# Skaarhoj_BI8-SE-C201.net
KiCad netlist of a schematic drawn in EAGLE
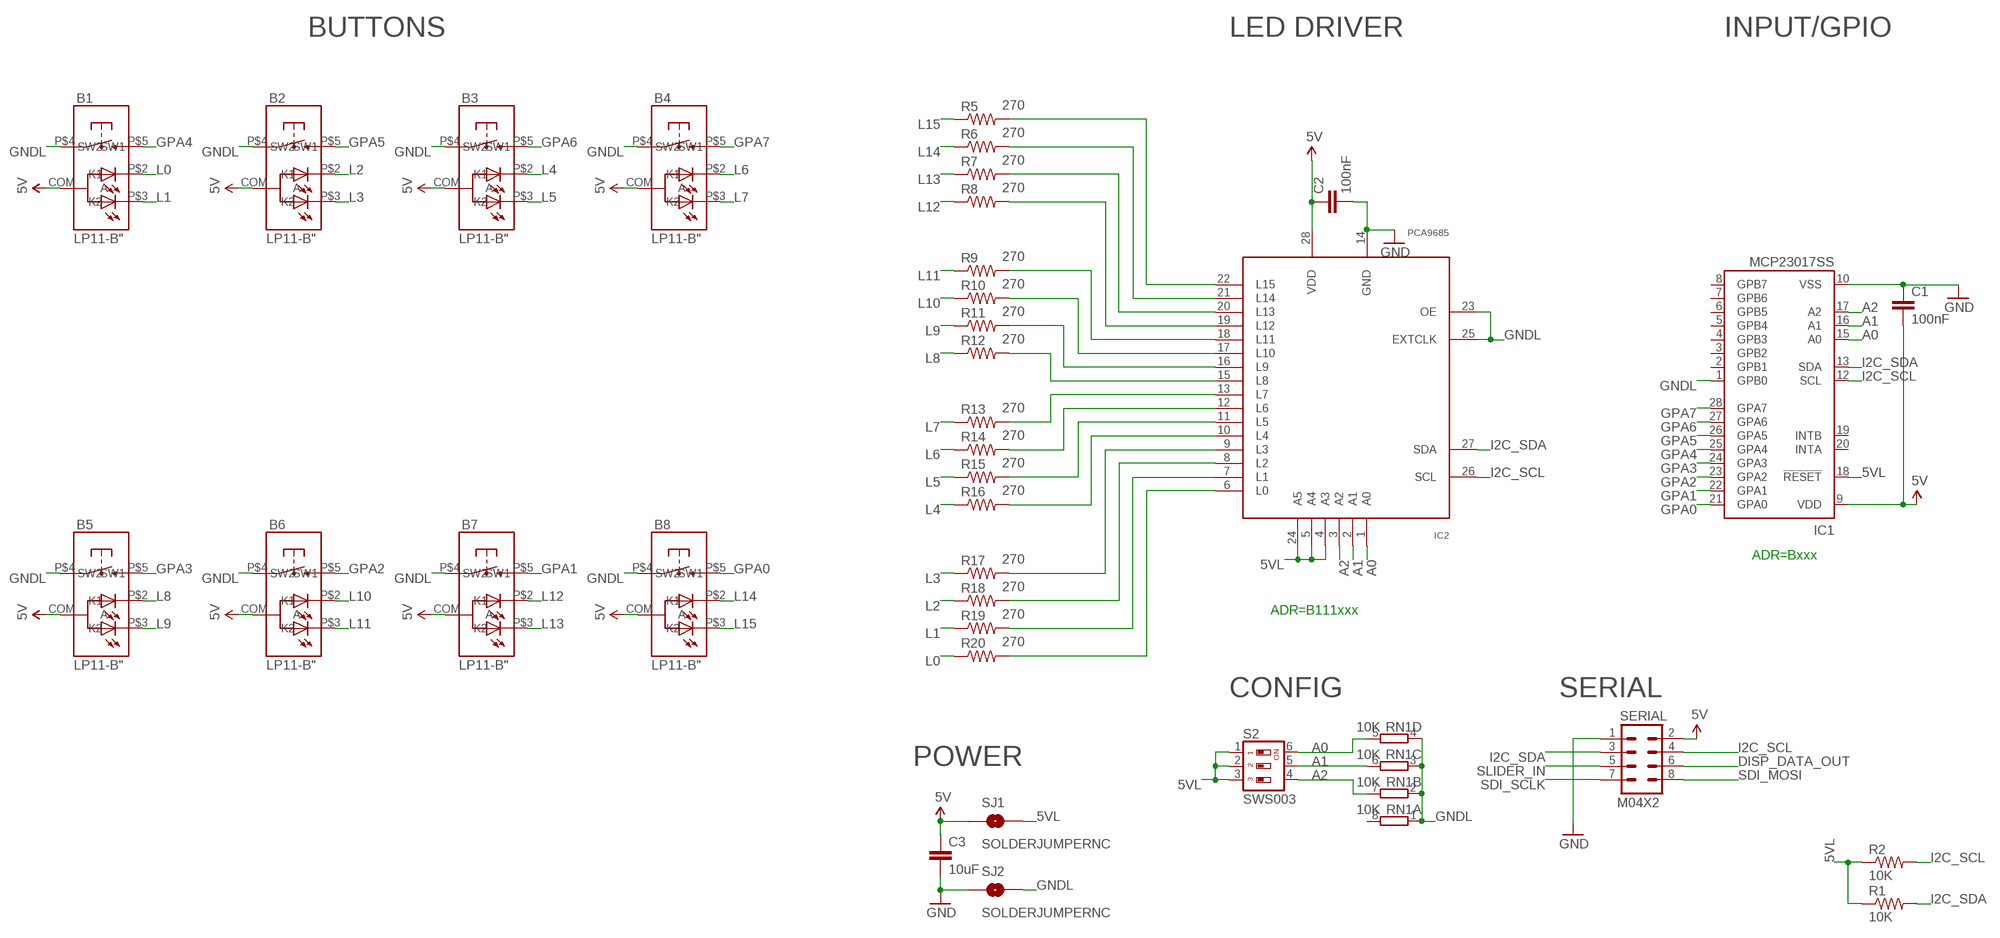
[diagram p0: schematic, sheet 1]

(export (version "E")
  (design (tool "Eeschema 10.0.6"))
  (components
    (comp (ref "B1")
      (value "LP11-B\"")
      (footprint "eagle-import:LP11")
      (libsource (lib "eagle-import") (part "LP11-B{dblquote}"))
    )
    (comp (ref "B2")
      (value "LP11-B\"")
      (footprint "eagle-import:LP11")
      (libsource (lib "eagle-import") (part "LP11-B{dblquote}"))
    )
    (comp (ref "B3")
      (value "LP11-B\"")
      (footprint "eagle-import:LP11")
      (libsource (lib "eagle-import") (part "LP11-B{dblquote}"))
    )
    (comp (ref "B4")
      (value "LP11-B\"")
      (footprint "eagle-import:LP11")
      (libsource (lib "eagle-import") (part "LP11-B{dblquote}"))
    )
    (comp (ref "B5")
      (value "LP11-B\"")
      (footprint "eagle-import:LP11")
      (libsource (lib "eagle-import") (part "LP11-B{dblquote}"))
    )
    (comp (ref "B6")
      (value "LP11-B\"")
      (footprint "eagle-import:LP11")
      (libsource (lib "eagle-import") (part "LP11-B{dblquote}"))
    )
    (comp (ref "B7")
      (value "LP11-B\"")
      (footprint "eagle-import:LP11")
      (libsource (lib "eagle-import") (part "LP11-B{dblquote}"))
    )
    (comp (ref "B8")
      (value "LP11-B\"")
      (footprint "eagle-import:LP11")
      (libsource (lib "eagle-import") (part "LP11-B{dblquote}"))
    )
    (comp (ref "C1")
      (value "100nF")
      (footprint "eagle-import:0603-CAP")
      (libsource (lib "eagle-import") (part "CAP0603-CAP"))
    )
    (comp (ref "C2")
      (value "100nF")
      (footprint "eagle-import:0603-CAP")
      (libsource (lib "eagle-import") (part "CAP0603-CAP"))
    )
    (comp (ref "C3")
      (value "10uF")
      (footprint "eagle-import:0805")
      (libsource (lib "eagle-import") (part "CAP0805"))
    )
    (comp (ref "IC1")
      (value "MCP23017SS")
      (footprint "eagle-import:SSOP28")
      (fields
        (field (name "MF") "MICROCHIP")
        (field (name "MPN") "MCP23017-E/SS")
        (field (name "MPN_1") "MCP23017-E/SS")
        (field (name "OC_FARNELL") "1467674")
        (field (name "OC_NEWARK") "31K2960")
      )
      (libsource (lib "eagle-import") (part "MCP23017SS"))
    )
    (comp (ref "IC2")
      (value "PCA9685")
      (footprint "eagle-import:TSSOP28")
      (libsource (lib "eagle-import") (part "PCA9685"))
    )
    (comp (ref "R1")
      (value "10K")
      (footprint "eagle-import:0603-RES")
      (libsource (lib "eagle-import") (part "RESISTOR0603-RES"))
    )
    (comp (ref "R2")
      (value "10K")
      (footprint "eagle-import:0603-RES")
      (libsource (lib "eagle-import") (part "RESISTOR0603-RES"))
    )
    (comp (ref "R5")
      (value "270")
      (footprint "eagle-import:0603-RES")
      (libsource (lib "eagle-import") (part "RESISTOR0603-RES"))
    )
    (comp (ref "R6")
      (value "270")
      (footprint "eagle-import:0603-RES")
      (libsource (lib "eagle-import") (part "RESISTOR0603-RES"))
    )
    (comp (ref "R7")
      (value "270")
      (footprint "eagle-import:0603-RES")
      (libsource (lib "eagle-import") (part "RESISTOR0603-RES"))
    )
    (comp (ref "R8")
      (value "270")
      (footprint "eagle-import:0603-RES")
      (libsource (lib "eagle-import") (part "RESISTOR0603-RES"))
    )
    (comp (ref "R9")
      (value "270")
      (footprint "eagle-import:0603-RES")
      (libsource (lib "eagle-import") (part "RESISTOR0603-RES"))
    )
    (comp (ref "R10")
      (value "270")
      (footprint "eagle-import:0603-RES")
      (libsource (lib "eagle-import") (part "RESISTOR0603-RES"))
    )
    (comp (ref "R11")
      (value "270")
      (footprint "eagle-import:0603-RES")
      (libsource (lib "eagle-import") (part "RESISTOR0603-RES"))
    )
    (comp (ref "R12")
      (value "270")
      (footprint "eagle-import:0603-RES")
      (libsource (lib "eagle-import") (part "RESISTOR0603-RES"))
    )
    (comp (ref "R13")
      (value "270")
      (footprint "eagle-import:0603-RES")
      (libsource (lib "eagle-import") (part "RESISTOR0603-RES"))
    )
    (comp (ref "R14")
      (value "270")
      (footprint "eagle-import:0603-RES")
      (libsource (lib "eagle-import") (part "RESISTOR0603-RES"))
    )
    (comp (ref "R15")
      (value "270")
      (footprint "eagle-import:0603-RES")
      (libsource (lib "eagle-import") (part "RESISTOR0603-RES"))
    )
    (comp (ref "R16")
      (value "270")
      (footprint "eagle-import:0603-RES")
      (libsource (lib "eagle-import") (part "RESISTOR0603-RES"))
    )
    (comp (ref "R17")
      (value "270")
      (footprint "eagle-import:0603-RES")
      (libsource (lib "eagle-import") (part "RESISTOR0603-RES"))
    )
    (comp (ref "R18")
      (value "270")
      (footprint "eagle-import:0603-RES")
      (libsource (lib "eagle-import") (part "RESISTOR0603-RES"))
    )
    (comp (ref "R19")
      (value "270")
      (footprint "eagle-import:0603-RES")
      (libsource (lib "eagle-import") (part "RESISTOR0603-RES"))
    )
    (comp (ref "R20")
      (value "270")
      (footprint "eagle-import:0603-RES")
      (libsource (lib "eagle-import") (part "RESISTOR0603-RES"))
    )
    (comp (ref "RN1")
      (value "10K")
      (footprint "eagle-import:CAY16_HAND")
      (libsource (lib "eagle-import") (part "4R-NCAY16"))
    )
    (comp (ref "S2")
      (value "SWS003")
      (footprint "eagle-import:SMS-003")
      (libsource (lib "eagle-import") (part "SWS003"))
    )
    (comp (ref "SERIAL")
      (value "M04X2")
      (footprint "eagle-import:2X4")
      (libsource (lib "eagle-import") (part "M04X2"))
    )
    (comp (ref "SJ1")
      (value "SOLDERJUMPERNC")
      (footprint "eagle-import:SJ_2S")
      (libsource (lib "eagle-import") (part "SOLDERJUMPERNC"))
    )
    (comp (ref "SJ2")
      (value "SOLDERJUMPERNC")
      (footprint "eagle-import:SJ_2S")
      (libsource (lib "eagle-import") (part "SOLDERJUMPERNC"))
    )
  )
  (nets
    (net (code "1") (name "/5VL") (class "Default")
      (node (ref "IC1") (pin "18") (pinfunction "~{RESET}_18") (pintype "input"))
      (node (ref "IC2") (pin "24") (pinfunction "A5_24") (pintype "input"))
      (node (ref "IC2") (pin "4") (pinfunction "A3_4") (pintype "input"))
      (node (ref "IC2") (pin "5") (pinfunction "A4_5") (pintype "input"))
      (node (ref "R1") (pin "1") (pinfunction "1_1") (pintype "passive"))
      (node (ref "R2") (pin "1") (pinfunction "1_1") (pintype "passive"))
      (node (ref "S2") (pin "1") (pinfunction "1_1") (pintype "passive"))
      (node (ref "S2") (pin "2") (pinfunction "2_2") (pintype "passive"))
      (node (ref "S2") (pin "3") (pinfunction "3_3") (pintype "passive"))
      (node (ref "SJ1") (pin "2") (pinfunction "2_2") (pintype "passive"))
    )
    (net (code "2") (name "/A0") (class "Default")
      (node (ref "IC1") (pin "15") (pinfunction "A0_15") (pintype "input"))
      (node (ref "IC2") (pin "1") (pinfunction "A0_1") (pintype "input"))
      (node (ref "RN1") (pin "5") (pinfunction "2_5") (pintype "passive"))
      (node (ref "S2") (pin "6") (pinfunction "6_6") (pintype "passive"))
    )
    (net (code "3") (name "/A1") (class "Default")
      (node (ref "IC1") (pin "16") (pinfunction "A1_16") (pintype "input"))
      (node (ref "IC2") (pin "2") (pinfunction "A1_2") (pintype "input"))
      (node (ref "RN1") (pin "6") (pinfunction "2_6") (pintype "passive"))
      (node (ref "S2") (pin "5") (pinfunction "5_5") (pintype "passive"))
    )
    (net (code "4") (name "/A2") (class "Default")
      (node (ref "IC1") (pin "17") (pinfunction "A2_17") (pintype "input"))
      (node (ref "IC2") (pin "3") (pinfunction "A2_3") (pintype "input"))
      (node (ref "RN1") (pin "7") (pinfunction "2_7") (pintype "passive"))
      (node (ref "S2") (pin "4") (pinfunction "4_4") (pintype "passive"))
    )
    (net (code "5") (name "/DISP_DATA_OUT") (class "Default")
      (node (ref "SERIAL") (pin "6") (pinfunction "6_6") (pintype "passive"))
    )
    (net (code "6") (name "/GNDL") (class "Default")
      (node (ref "B1") (pin "P$4") (pinfunction "SW1_P$4") (pintype "bidirectional"))
      (node (ref "B2") (pin "P$4") (pinfunction "SW1_P$4") (pintype "bidirectional"))
      (node (ref "B3") (pin "P$4") (pinfunction "SW1_P$4") (pintype "bidirectional"))
      (node (ref "B4") (pin "P$4") (pinfunction "SW1_P$4") (pintype "bidirectional"))
      (node (ref "B5") (pin "P$4") (pinfunction "SW1_P$4") (pintype "bidirectional"))
      (node (ref "B6") (pin "P$4") (pinfunction "SW1_P$4") (pintype "bidirectional"))
      (node (ref "B7") (pin "P$4") (pinfunction "SW1_P$4") (pintype "bidirectional"))
      (node (ref "B8") (pin "P$4") (pinfunction "SW1_P$4") (pintype "bidirectional"))
      (node (ref "IC1") (pin "1") (pinfunction "GPB0_1") (pintype "bidirectional"))
      (node (ref "IC2") (pin "23") (pinfunction "OE_23") (pintype "input"))
      (node (ref "IC2") (pin "25") (pinfunction "EXTCLK_25") (pintype "input"))
      (node (ref "RN1") (pin "1") (pinfunction "1_1") (pintype "passive"))
      (node (ref "RN1") (pin "2") (pinfunction "1_2") (pintype "passive"))
      (node (ref "RN1") (pin "3") (pinfunction "1_3") (pintype "passive"))
      (node (ref "RN1") (pin "4") (pinfunction "1_4") (pintype "passive"))
      (node (ref "SJ2") (pin "2") (pinfunction "2_2") (pintype "passive"))
    )
    (net (code "7") (name "/GPA0") (class "Default")
      (node (ref "B8") (pin "P$5") (pinfunction "SW2_P$5") (pintype "bidirectional"))
      (node (ref "IC1") (pin "21") (pinfunction "GPA0_21") (pintype "bidirectional"))
    )
    (net (code "8") (name "/GPA1") (class "Default")
      (node (ref "B7") (pin "P$5") (pinfunction "SW2_P$5") (pintype "bidirectional"))
      (node (ref "IC1") (pin "22") (pinfunction "GPA1_22") (pintype "bidirectional"))
    )
    (net (code "9") (name "/GPA2") (class "Default")
      (node (ref "B6") (pin "P$5") (pinfunction "SW2_P$5") (pintype "bidirectional"))
      (node (ref "IC1") (pin "23") (pinfunction "GPA2_23") (pintype "bidirectional"))
    )
    (net (code "10") (name "/GPA3") (class "Default")
      (node (ref "B5") (pin "P$5") (pinfunction "SW2_P$5") (pintype "bidirectional"))
      (node (ref "IC1") (pin "24") (pinfunction "GPA3_24") (pintype "bidirectional"))
    )
    (net (code "11") (name "/GPA4") (class "Default")
      (node (ref "B1") (pin "P$5") (pinfunction "SW2_P$5") (pintype "bidirectional"))
      (node (ref "IC1") (pin "25") (pinfunction "GPA4_25") (pintype "bidirectional"))
    )
    (net (code "12") (name "/GPA5") (class "Default")
      (node (ref "B2") (pin "P$5") (pinfunction "SW2_P$5") (pintype "bidirectional"))
      (node (ref "IC1") (pin "26") (pinfunction "GPA5_26") (pintype "bidirectional"))
    )
    (net (code "13") (name "/GPA6") (class "Default")
      (node (ref "B3") (pin "P$5") (pinfunction "SW2_P$5") (pintype "bidirectional"))
      (node (ref "IC1") (pin "27") (pinfunction "GPA6_27") (pintype "bidirectional"))
    )
    (net (code "14") (name "/GPA7") (class "Default")
      (node (ref "B4") (pin "P$5") (pinfunction "SW2_P$5") (pintype "bidirectional"))
      (node (ref "IC1") (pin "28") (pinfunction "GPA7_28") (pintype "bidirectional"))
    )
    (net (code "15") (name "/I2C_SCL") (class "Default")
      (node (ref "IC1") (pin "12") (pinfunction "SCL_12") (pintype "input"))
      (node (ref "IC2") (pin "26") (pinfunction "SCL_26") (pintype "input"))
      (node (ref "R2") (pin "2") (pinfunction "2_2") (pintype "passive"))
      (node (ref "SERIAL") (pin "4") (pinfunction "4_4") (pintype "passive"))
    )
    (net (code "16") (name "/I2C_SDA") (class "Default")
      (node (ref "IC1") (pin "13") (pinfunction "SDA_13") (pintype "bidirectional"))
      (node (ref "IC2") (pin "27") (pinfunction "SDA_27") (pintype "input"))
      (node (ref "R1") (pin "2") (pinfunction "2_2") (pintype "passive"))
      (node (ref "SERIAL") (pin "3") (pinfunction "3_3") (pintype "passive"))
    )
    (net (code "17") (name "/L0") (class "Default")
      (node (ref "B1") (pin "P$2") (pinfunction "K1_P$2") (pintype "bidirectional"))
      (node (ref "R20") (pin "1") (pinfunction "1_1") (pintype "passive"))
    )
    (net (code "18") (name "/L1") (class "Default")
      (node (ref "B1") (pin "P$3") (pinfunction "K2_P$3") (pintype "bidirectional"))
      (node (ref "R19") (pin "1") (pinfunction "1_1") (pintype "passive"))
    )
    (net (code "19") (name "/L2") (class "Default")
      (node (ref "B2") (pin "P$2") (pinfunction "K1_P$2") (pintype "bidirectional"))
      (node (ref "R18") (pin "1") (pinfunction "1_1") (pintype "passive"))
    )
    (net (code "20") (name "/L3") (class "Default")
      (node (ref "B2") (pin "P$3") (pinfunction "K2_P$3") (pintype "bidirectional"))
      (node (ref "R17") (pin "1") (pinfunction "1_1") (pintype "passive"))
    )
    (net (code "21") (name "/L4") (class "Default")
      (node (ref "B3") (pin "P$2") (pinfunction "K1_P$2") (pintype "bidirectional"))
      (node (ref "R16") (pin "1") (pinfunction "1_1") (pintype "passive"))
    )
    (net (code "22") (name "/L5") (class "Default")
      (node (ref "B3") (pin "P$3") (pinfunction "K2_P$3") (pintype "bidirectional"))
      (node (ref "R15") (pin "1") (pinfunction "1_1") (pintype "passive"))
    )
    (net (code "23") (name "/L6") (class "Default")
      (node (ref "B4") (pin "P$2") (pinfunction "K1_P$2") (pintype "bidirectional"))
      (node (ref "R14") (pin "1") (pinfunction "1_1") (pintype "passive"))
    )
    (net (code "24") (name "/L7") (class "Default")
      (node (ref "B4") (pin "P$3") (pinfunction "K2_P$3") (pintype "bidirectional"))
      (node (ref "R13") (pin "1") (pinfunction "1_1") (pintype "passive"))
    )
    (net (code "25") (name "/L8") (class "Default")
      (node (ref "B5") (pin "P$2") (pinfunction "K1_P$2") (pintype "bidirectional"))
      (node (ref "R12") (pin "1") (pinfunction "1_1") (pintype "passive"))
    )
    (net (code "26") (name "/L9") (class "Default")
      (node (ref "B5") (pin "P$3") (pinfunction "K2_P$3") (pintype "bidirectional"))
      (node (ref "R11") (pin "1") (pinfunction "1_1") (pintype "passive"))
    )
    (net (code "27") (name "/L10") (class "Default")
      (node (ref "B6") (pin "P$2") (pinfunction "K1_P$2") (pintype "bidirectional"))
      (node (ref "R10") (pin "1") (pinfunction "1_1") (pintype "passive"))
    )
    (net (code "28") (name "/L11") (class "Default")
      (node (ref "B6") (pin "P$3") (pinfunction "K2_P$3") (pintype "bidirectional"))
      (node (ref "R9") (pin "1") (pinfunction "1_1") (pintype "passive"))
    )
    (net (code "29") (name "/L12") (class "Default")
      (node (ref "B7") (pin "P$2") (pinfunction "K1_P$2") (pintype "bidirectional"))
      (node (ref "R8") (pin "1") (pinfunction "1_1") (pintype "passive"))
    )
    (net (code "30") (name "/L13") (class "Default")
      (node (ref "B7") (pin "P$3") (pinfunction "K2_P$3") (pintype "bidirectional"))
      (node (ref "R7") (pin "1") (pinfunction "1_1") (pintype "passive"))
    )
    (net (code "31") (name "/L14") (class "Default")
      (node (ref "B8") (pin "P$2") (pinfunction "K1_P$2") (pintype "bidirectional"))
      (node (ref "R6") (pin "1") (pinfunction "1_1") (pintype "passive"))
    )
    (net (code "32") (name "/L15") (class "Default")
      (node (ref "B8") (pin "P$3") (pinfunction "K2_P$3") (pintype "bidirectional"))
      (node (ref "R5") (pin "1") (pinfunction "1_1") (pintype "passive"))
    )
    (net (code "33") (name "/SDI_MOSI") (class "Default")
      (node (ref "SERIAL") (pin "8") (pinfunction "8_8") (pintype "passive"))
    )
    (net (code "34") (name "/SDI_SCLK") (class "Default")
      (node (ref "SERIAL") (pin "7") (pinfunction "7_7") (pintype "passive"))
    )
    (net (code "35") (name "/SLIDER_IN") (class "Default")
      (node (ref "SERIAL") (pin "5") (pinfunction "5_5") (pintype "passive"))
    )
    (net (code "36") (name "5V") (class "Default")
      (node (ref "B1") (pin "COM") (pinfunction "A_COM") (pintype "bidirectional"))
      (node (ref "B2") (pin "COM") (pinfunction "A_COM") (pintype "bidirectional"))
      (node (ref "B3") (pin "COM") (pinfunction "A_COM") (pintype "bidirectional"))
      (node (ref "B4") (pin "COM") (pinfunction "A_COM") (pintype "bidirectional"))
      (node (ref "B5") (pin "COM") (pinfunction "A_COM") (pintype "bidirectional"))
      (node (ref "B6") (pin "COM") (pinfunction "A_COM") (pintype "bidirectional"))
      (node (ref "B7") (pin "COM") (pinfunction "A_COM") (pintype "bidirectional"))
      (node (ref "B8") (pin "COM") (pinfunction "A_COM") (pintype "bidirectional"))
      (node (ref "C1") (pin "2") (pinfunction "2_2") (pintype "passive"))
      (node (ref "C2") (pin "1") (pinfunction "1_1") (pintype "passive"))
      (node (ref "C3") (pin "1") (pinfunction "1_1") (pintype "passive"))
      (node (ref "IC1") (pin "9") (pinfunction "VDD_9") (pintype "power_in"))
      (node (ref "IC2") (pin "28") (pinfunction "VDD_28") (pintype "power_in"))
      (node (ref "SERIAL") (pin "2") (pinfunction "2_2") (pintype "passive"))
      (node (ref "SJ1") (pin "1") (pinfunction "1_1") (pintype "passive"))
    )
    (net (code "37") (name "GND") (class "Default")
      (node (ref "C1") (pin "1") (pinfunction "1_1") (pintype "passive"))
      (node (ref "C2") (pin "2") (pinfunction "2_2") (pintype "passive"))
      (node (ref "C3") (pin "2") (pinfunction "2_2") (pintype "passive"))
      (node (ref "IC1") (pin "10") (pinfunction "VSS_10") (pintype "power_in"))
      (node (ref "IC2") (pin "14") (pinfunction "GND_14") (pintype "power_in"))
      (node (ref "SERIAL") (pin "1") (pinfunction "1_1") (pintype "passive"))
      (node (ref "SJ2") (pin "1") (pinfunction "1_1") (pintype "passive"))
    )
    (net (code "38") (name "Net-(IC2-L0)") (class "Default")
      (node (ref "IC2") (pin "6") (pinfunction "L0_6") (pintype "output"))
      (node (ref "R20") (pin "2") (pinfunction "2_2") (pintype "passive"))
    )
    (net (code "39") (name "Net-(IC2-L1)") (class "Default")
      (node (ref "IC2") (pin "7") (pinfunction "L1_7") (pintype "output"))
      (node (ref "R19") (pin "2") (pinfunction "2_2") (pintype "passive"))
    )
    (net (code "40") (name "Net-(IC2-L2)") (class "Default")
      (node (ref "IC2") (pin "8") (pinfunction "L2_8") (pintype "output"))
      (node (ref "R18") (pin "2") (pinfunction "2_2") (pintype "passive"))
    )
    (net (code "41") (name "Net-(IC2-L3)") (class "Default")
      (node (ref "IC2") (pin "9") (pinfunction "L3_9") (pintype "output"))
      (node (ref "R17") (pin "2") (pinfunction "2_2") (pintype "passive"))
    )
    (net (code "42") (name "Net-(IC2-L4)") (class "Default")
      (node (ref "IC2") (pin "10") (pinfunction "L4_10") (pintype "output"))
      (node (ref "R16") (pin "2") (pinfunction "2_2") (pintype "passive"))
    )
    (net (code "43") (name "Net-(IC2-L5)") (class "Default")
      (node (ref "IC2") (pin "11") (pinfunction "L5_11") (pintype "output"))
      (node (ref "R15") (pin "2") (pinfunction "2_2") (pintype "passive"))
    )
    (net (code "44") (name "Net-(IC2-L6)") (class "Default")
      (node (ref "IC2") (pin "12") (pinfunction "L6_12") (pintype "output"))
      (node (ref "R14") (pin "2") (pinfunction "2_2") (pintype "passive"))
    )
    (net (code "45") (name "Net-(IC2-L7)") (class "Default")
      (node (ref "IC2") (pin "13") (pinfunction "L7_13") (pintype "output"))
      (node (ref "R13") (pin "2") (pinfunction "2_2") (pintype "passive"))
    )
    (net (code "46") (name "Net-(IC2-L8)") (class "Default")
      (node (ref "IC2") (pin "15") (pinfunction "L8_15") (pintype "output"))
      (node (ref "R12") (pin "2") (pinfunction "2_2") (pintype "passive"))
    )
    (net (code "47") (name "Net-(IC2-L9)") (class "Default")
      (node (ref "IC2") (pin "16") (pinfunction "L9_16") (pintype "output"))
      (node (ref "R11") (pin "2") (pinfunction "2_2") (pintype "passive"))
    )
    (net (code "48") (name "Net-(IC2-L10)") (class "Default")
      (node (ref "IC2") (pin "17") (pinfunction "L10_17") (pintype "output"))
      (node (ref "R10") (pin "2") (pinfunction "2_2") (pintype "passive"))
    )
    (net (code "49") (name "Net-(IC2-L11)") (class "Default")
      (node (ref "IC2") (pin "18") (pinfunction "L11_18") (pintype "output"))
      (node (ref "R9") (pin "2") (pinfunction "2_2") (pintype "passive"))
    )
    (net (code "50") (name "Net-(IC2-L12)") (class "Default")
      (node (ref "IC2") (pin "19") (pinfunction "L12_19") (pintype "output"))
      (node (ref "R8") (pin "2") (pinfunction "2_2") (pintype "passive"))
    )
    (net (code "51") (name "Net-(IC2-L13)") (class "Default")
      (node (ref "IC2") (pin "20") (pinfunction "L13_20") (pintype "output"))
      (node (ref "R7") (pin "2") (pinfunction "2_2") (pintype "passive"))
    )
    (net (code "52") (name "Net-(IC2-L14)") (class "Default")
      (node (ref "IC2") (pin "21") (pinfunction "L14_21") (pintype "output"))
      (node (ref "R6") (pin "2") (pinfunction "2_2") (pintype "passive"))
    )
    (net (code "53") (name "Net-(IC2-L15)") (class "Default")
      (node (ref "IC2") (pin "22") (pinfunction "L15_22") (pintype "output"))
      (node (ref "R5") (pin "2") (pinfunction "2_2") (pintype "passive"))
    )
    (net (code "54") (name "unconnected-(IC1-GPB1-Pad2)") (class "Default")
      (node (ref "IC1") (pin "2") (pinfunction "GPB1_2") (pintype "bidirectional"))
    )
    (net (code "55") (name "unconnected-(IC1-GPB2-Pad3)") (class "Default")
      (node (ref "IC1") (pin "3") (pinfunction "GPB2_3") (pintype "bidirectional"))
    )
    (net (code "56") (name "unconnected-(IC1-GPB3-Pad4)") (class "Default")
      (node (ref "IC1") (pin "4") (pinfunction "GPB3_4") (pintype "bidirectional"))
    )
    (net (code "57") (name "unconnected-(IC1-GPB4-Pad5)") (class "Default")
      (node (ref "IC1") (pin "5") (pinfunction "GPB4_5") (pintype "bidirectional"))
    )
    (net (code "58") (name "unconnected-(IC1-GPB5-Pad6)") (class "Default")
      (node (ref "IC1") (pin "6") (pinfunction "GPB5_6") (pintype "bidirectional"))
    )
    (net (code "59") (name "unconnected-(IC1-GPB6-Pad7)") (class "Default")
      (node (ref "IC1") (pin "7") (pinfunction "GPB6_7") (pintype "bidirectional"))
    )
    (net (code "60") (name "unconnected-(IC1-GPB7-Pad8)") (class "Default")
      (node (ref "IC1") (pin "8") (pinfunction "GPB7_8") (pintype "bidirectional"))
    )
    (net (code "61") (name "unconnected-(IC1-INTA-Pad20)") (class "Default")
      (node (ref "IC1") (pin "20") (pinfunction "INTA_20") (pintype "output"))
    )
    (net (code "62") (name "unconnected-(IC1-INTB-Pad19)") (class "Default")
      (node (ref "IC1") (pin "19") (pinfunction "INTB_19") (pintype "output"))
    )
    (net (code "63") (name "unconnected-(RN1A-2-Pad8)") (class "Default")
      (node (ref "RN1") (pin "8") (pinfunction "2_8") (pintype "passive"))
    )
  )
)
